# ScanDriver.net
KiCad netlist of a schematic drawn in EAGLE
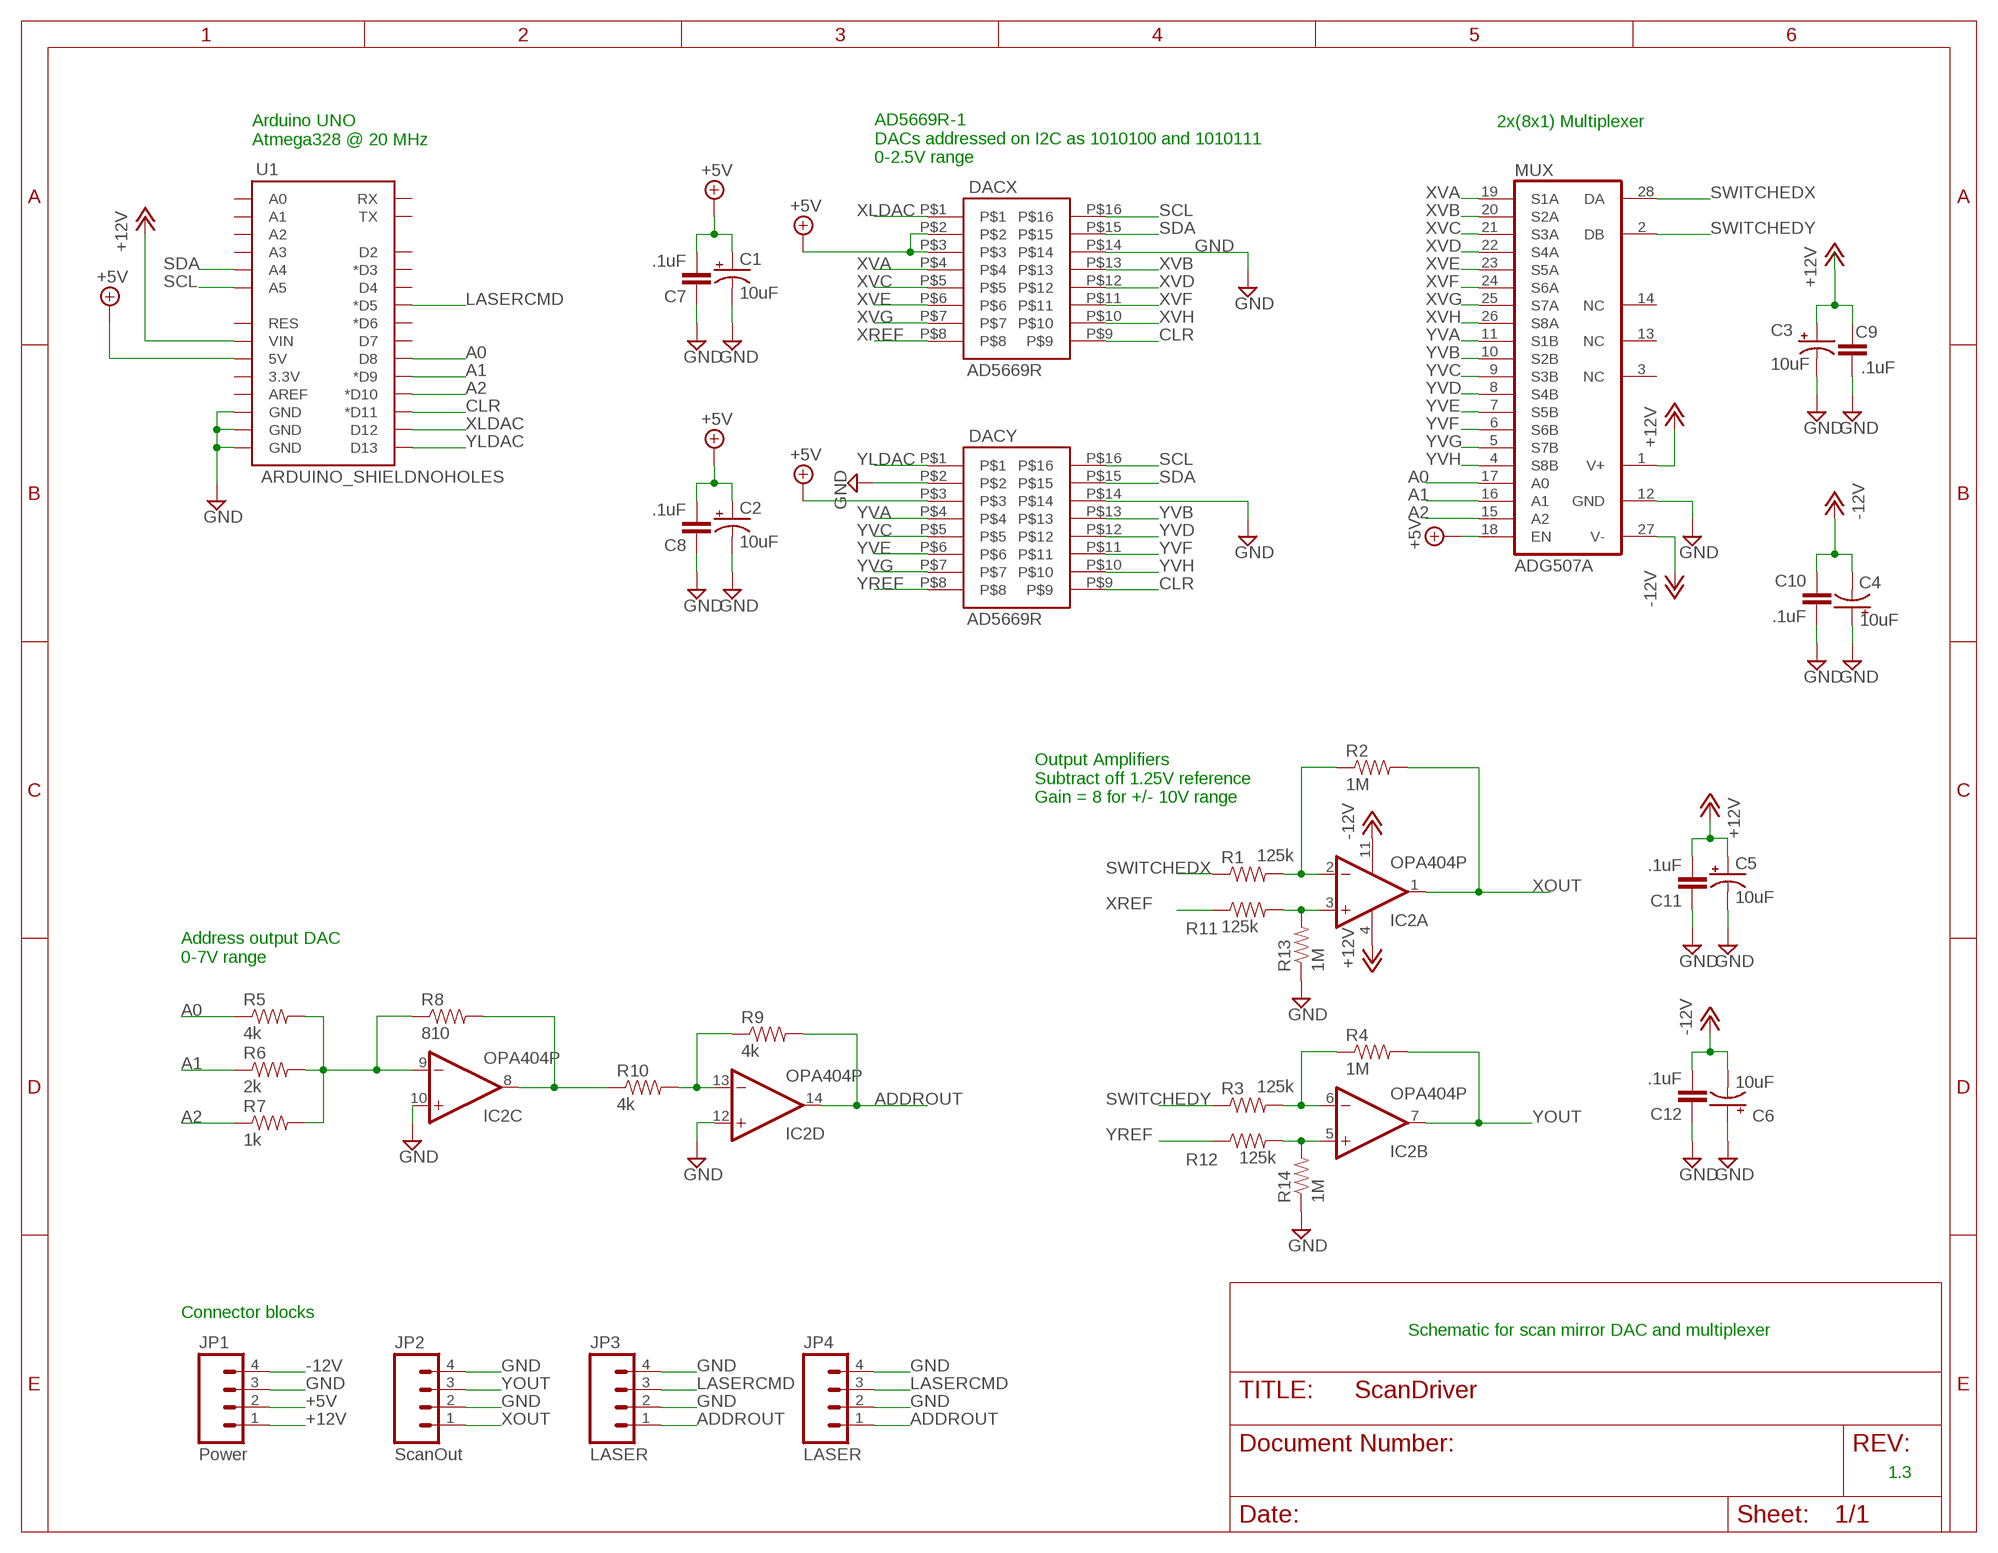
[diagram p0: schematic, sheet 1]

(export (version "E")
  (design (tool "Eeschema 10.0.6"))
  (components
    (comp (ref "C1")
      (value "10uF")
      (footprint "eagle-import:CPOL-RADIAL-10UF-25V")
      (libsource (lib "eagle-import") (part "CAP_POLPTH2"))
    )
    (comp (ref "C2")
      (value "10uF")
      (footprint "eagle-import:CPOL-RADIAL-10UF-25V")
      (libsource (lib "eagle-import") (part "CAP_POLPTH2"))
    )
    (comp (ref "C3")
      (value "10uF")
      (footprint "eagle-import:CPOL-RADIAL-10UF-25V")
      (libsource (lib "eagle-import") (part "CAP_POLPTH2"))
    )
    (comp (ref "C4")
      (value "10uF")
      (footprint "eagle-import:CPOL-RADIAL-10UF-25V")
      (libsource (lib "eagle-import") (part "CAP_POLPTH2"))
    )
    (comp (ref "C5")
      (value "10uF")
      (footprint "eagle-import:CPOL-RADIAL-10UF-25V")
      (libsource (lib "eagle-import") (part "CAP_POLPTH2"))
    )
    (comp (ref "C6")
      (value "10uF")
      (footprint "eagle-import:CPOL-RADIAL-10UF-25V")
      (libsource (lib "eagle-import") (part "CAP_POLPTH2"))
    )
    (comp (ref "C7")
      (value ".1uF")
      (footprint "eagle-import:CAP-PTH-SMALL-KIT")
      (libsource (lib "eagle-import") (part "CAPKIT"))
    )
    (comp (ref "C8")
      (value ".1uF")
      (footprint "eagle-import:CAP-PTH-SMALL-KIT")
      (libsource (lib "eagle-import") (part "CAPKIT"))
    )
    (comp (ref "C9")
      (value ".1uF")
      (footprint "eagle-import:CAP-PTH-SMALL-KIT")
      (libsource (lib "eagle-import") (part "CAPKIT"))
    )
    (comp (ref "C10")
      (value ".1uF")
      (footprint "eagle-import:CAP-PTH-SMALL-KIT")
      (libsource (lib "eagle-import") (part "CAPKIT"))
    )
    (comp (ref "C11")
      (value ".1uF")
      (footprint "eagle-import:CAP-PTH-SMALL-KIT")
      (libsource (lib "eagle-import") (part "CAPKIT"))
    )
    (comp (ref "C12")
      (value ".1uF")
      (footprint "eagle-import:CAP-PTH-SMALL-KIT")
      (libsource (lib "eagle-import") (part "CAPKIT"))
    )
    (comp (ref "DACX")
      (value "AD5669R")
      (footprint "eagle-import:SSOP16")
      (libsource (lib "eagle-import") (part "SSOP16"))
    )
    (comp (ref "DACY")
      (value "AD5669R")
      (footprint "eagle-import:SSOP16")
      (libsource (lib "eagle-import") (part "SSOP16"))
    )
    (comp (ref "IC2")
      (value "OPA404P")
      (footprint "eagle-import:DIL14")
      (libsource (lib "eagle-import") (part "OPA404P"))
    )
    (comp (ref "JP1")
      (value "Power")
      (footprint "eagle-import:MOLEX-1X4")
      (libsource (lib "eagle-import") (part "M04POLAR"))
    )
    (comp (ref "JP2")
      (value "ScanOut")
      (footprint "eagle-import:MOLEX-1X4")
      (libsource (lib "eagle-import") (part "M04POLAR"))
    )
    (comp (ref "JP3")
      (value "LASER")
      (footprint "eagle-import:MOLEX-1X4")
      (libsource (lib "eagle-import") (part "M04POLAR"))
    )
    (comp (ref "JP4")
      (value "LASER")
      (footprint "eagle-import:MOLEX-1X4")
      (libsource (lib "eagle-import") (part "M04POLAR"))
    )
    (comp (ref "MUX")
      (value "ADG507A")
      (footprint "eagle-import:DIL28-6")
      (fields (field (name "MPN") "DG507ACJ+"))
      (libsource (lib "eagle-import") (part "DG507ACJ"))
    )
    (comp (ref "R1")
      (value "125k")
      (footprint "eagle-import:AXIAL-0.4")
      (libsource (lib "eagle-import") (part "RESISTORPTH-1/4W"))
    )
    (comp (ref "R2")
      (value "1M")
      (footprint "eagle-import:AXIAL-0.4")
      (libsource (lib "eagle-import") (part "RESISTORPTH-1/4W"))
    )
    (comp (ref "R3")
      (value "125k")
      (footprint "eagle-import:AXIAL-0.4")
      (libsource (lib "eagle-import") (part "RESISTORPTH-1/4W"))
    )
    (comp (ref "R4")
      (value "1M")
      (footprint "eagle-import:AXIAL-0.4")
      (libsource (lib "eagle-import") (part "RESISTORPTH-1/4W"))
    )
    (comp (ref "R5")
      (value "4k")
      (footprint "eagle-import:AXIAL-0.4")
      (libsource (lib "eagle-import") (part "RESISTORPTH-1/4W"))
    )
    (comp (ref "R6")
      (value "2k")
      (footprint "eagle-import:AXIAL-0.4")
      (libsource (lib "eagle-import") (part "RESISTORPTH-1/4W"))
    )
    (comp (ref "R7")
      (value "1k")
      (footprint "eagle-import:AXIAL-0.4")
      (libsource (lib "eagle-import") (part "RESISTORPTH-1/4W"))
    )
    (comp (ref "R8")
      (value "810")
      (footprint "eagle-import:AXIAL-0.4")
      (libsource (lib "eagle-import") (part "RESISTORPTH-1/4W"))
    )
    (comp (ref "R9")
      (value "4k")
      (footprint "eagle-import:AXIAL-0.4")
      (libsource (lib "eagle-import") (part "RESISTORPTH-1/4W"))
    )
    (comp (ref "R10")
      (value "4k")
      (footprint "eagle-import:AXIAL-0.4")
      (libsource (lib "eagle-import") (part "RESISTORPTH-1/4W"))
    )
    (comp (ref "R11")
      (value "125k")
      (footprint "eagle-import:AXIAL-0.4")
      (libsource (lib "eagle-import") (part "RESISTORPTH-1/4W"))
    )
    (comp (ref "R12")
      (value "125k")
      (footprint "eagle-import:AXIAL-0.4")
      (libsource (lib "eagle-import") (part "RESISTORPTH-1/4W"))
    )
    (comp (ref "R13")
      (value "1M")
      (footprint "eagle-import:AXIAL-0.4")
      (libsource (lib "eagle-import") (part "RESISTORPTH-1/4W"))
    )
    (comp (ref "R14")
      (value "1M")
      (footprint "eagle-import:AXIAL-0.4")
      (libsource (lib "eagle-import") (part "RESISTORPTH-1/4W"))
    )
    (comp (ref "U1")
      (value "ARDUINO_SHIELDNOHOLES")
      (footprint "eagle-import:DUEMILANOVE_SHIELD_NOHOLES")
      (libsource (lib "eagle-import") (part "ARDUINO_SHIELDNOHOLES"))
    )
  )
  (nets
    (net (code "1") (name "+5V") (class "Default")
      (node (ref "C1") (pin "1") (pinfunction "+_1") (pintype "passive"))
      (node (ref "C2") (pin "1") (pinfunction "+_1") (pintype "passive"))
      (node (ref "C7") (pin "2") (pinfunction "2_2") (pintype "passive"))
      (node (ref "C8") (pin "2") (pinfunction "2_2") (pintype "passive"))
      (node (ref "DACX") (pin "P$2") (pinfunction "P$2_P$2") (pintype "bidirectional"))
      (node (ref "DACX") (pin "P$3") (pinfunction "P$3_P$3") (pintype "bidirectional"))
      (node (ref "DACY") (pin "P$3") (pinfunction "P$3_P$3") (pintype "bidirectional"))
      (node (ref "JP1") (pin "2") (pinfunction "2_2") (pintype "passive"))
      (node (ref "MUX") (pin "18") (pinfunction "EN_18") (pintype "input"))
      (node (ref "U1") (pin "5V") (pinfunction "5V_5V") (pintype "bidirectional"))
    )
    (net (code "2") (name "+12V") (class "Default")
      (node (ref "C11") (pin "2") (pinfunction "2_2") (pintype "passive"))
      (node (ref "C3") (pin "1") (pinfunction "+_1") (pintype "passive"))
      (node (ref "C5") (pin "1") (pinfunction "+_1") (pintype "passive"))
      (node (ref "C9") (pin "2") (pinfunction "2_2") (pintype "passive"))
      (node (ref "IC2") (pin "4") (pinfunction "V+_4") (pintype "power_in"))
      (node (ref "JP1") (pin "1") (pinfunction "1_1") (pintype "passive"))
      (node (ref "MUX") (pin "1") (pinfunction "V+_1") (pintype "power_in"))
      (node (ref "U1") (pin "VIN") (pinfunction "VIN_VIN") (pintype "bidirectional"))
    )
    (net (code "3") (name "-12V") (class "Default")
      (node (ref "C10") (pin "2") (pinfunction "2_2") (pintype "passive"))
      (node (ref "C12") (pin "2") (pinfunction "2_2") (pintype "passive"))
      (node (ref "C4") (pin "2") (pinfunction "-_2") (pintype "passive"))
      (node (ref "C6") (pin "2") (pinfunction "-_2") (pintype "passive"))
      (node (ref "IC2") (pin "11") (pinfunction "V-_11") (pintype "power_in"))
      (node (ref "JP1") (pin "4") (pinfunction "4_4") (pintype "passive"))
      (node (ref "MUX") (pin "27") (pinfunction "V-_27") (pintype "power_in"))
    )
    (net (code "4") (name "/A0") (class "Default")
      (node (ref "MUX") (pin "17") (pinfunction "A0_17") (pintype "input"))
      (node (ref "R5") (pin "P$1") (pinfunction "1_P$1") (pintype "passive"))
      (node (ref "U1") (pin "D8") (pinfunction "D8_D8") (pintype "bidirectional"))
    )
    (net (code "5") (name "/A1") (class "Default")
      (node (ref "MUX") (pin "16") (pinfunction "A1_16") (pintype "input"))
      (node (ref "R6") (pin "P$1") (pinfunction "1_P$1") (pintype "passive"))
      (node (ref "U1") (pin "D9") (pinfunction "*D9_D9") (pintype "bidirectional"))
    )
    (net (code "6") (name "/A2") (class "Default")
      (node (ref "MUX") (pin "15") (pinfunction "A2_15") (pintype "input"))
      (node (ref "R7") (pin "P$1") (pinfunction "1_P$1") (pintype "passive"))
      (node (ref "U1") (pin "D10") (pinfunction "*D10_D10") (pintype "bidirectional"))
    )
    (net (code "7") (name "/ADDROUT") (class "Default")
      (node (ref "IC2") (pin "14") (pinfunction "OUT_14") (pintype "output"))
      (node (ref "JP3") (pin "1") (pinfunction "1_1") (pintype "passive"))
      (node (ref "JP4") (pin "1") (pinfunction "1_1") (pintype "passive"))
      (node (ref "R9") (pin "P$2") (pinfunction "2_P$2") (pintype "passive"))
    )
    (net (code "8") (name "/CLR") (class "Default")
      (node (ref "DACX") (pin "P$9") (pinfunction "P$9_P$9") (pintype "bidirectional"))
      (node (ref "DACY") (pin "P$9") (pinfunction "P$9_P$9") (pintype "bidirectional"))
      (node (ref "U1") (pin "D11") (pinfunction "*D11_D11") (pintype "bidirectional"))
    )
    (net (code "9") (name "/LASERCMD") (class "Default")
      (node (ref "JP3") (pin "3") (pinfunction "3_3") (pintype "passive"))
      (node (ref "JP4") (pin "3") (pinfunction "3_3") (pintype "passive"))
      (node (ref "U1") (pin "D5") (pinfunction "*D5_D5") (pintype "bidirectional"))
    )
    (net (code "10") (name "/SCL") (class "Default")
      (node (ref "DACX") (pin "P$16") (pinfunction "P$16_P$16") (pintype "bidirectional"))
      (node (ref "DACY") (pin "P$16") (pinfunction "P$16_P$16") (pintype "bidirectional"))
      (node (ref "U1") (pin "A5") (pinfunction "A5_A5") (pintype "bidirectional"))
    )
    (net (code "11") (name "/SDA") (class "Default")
      (node (ref "DACX") (pin "P$15") (pinfunction "P$15_P$15") (pintype "bidirectional"))
      (node (ref "DACY") (pin "P$15") (pinfunction "P$15_P$15") (pintype "bidirectional"))
      (node (ref "U1") (pin "A4") (pinfunction "A4_A4") (pintype "bidirectional"))
    )
    (net (code "12") (name "/SWITCHEDX") (class "Default")
      (node (ref "MUX") (pin "28") (pinfunction "DA_28") (pintype "passive"))
      (node (ref "R1") (pin "P$1") (pinfunction "1_P$1") (pintype "passive"))
    )
    (net (code "13") (name "/SWITCHEDY") (class "Default")
      (node (ref "MUX") (pin "2") (pinfunction "DB_2") (pintype "passive"))
      (node (ref "R3") (pin "P$1") (pinfunction "1_P$1") (pintype "passive"))
    )
    (net (code "14") (name "/XLDAC") (class "Default")
      (node (ref "DACX") (pin "P$1") (pinfunction "P$1_P$1") (pintype "bidirectional"))
      (node (ref "U1") (pin "D12") (pinfunction "D12_D12") (pintype "bidirectional"))
    )
    (net (code "15") (name "/XOUT") (class "Default")
      (node (ref "IC2") (pin "1") (pinfunction "OUT_1") (pintype "output"))
      (node (ref "JP2") (pin "1") (pinfunction "1_1") (pintype "passive"))
      (node (ref "R2") (pin "P$2") (pinfunction "2_P$2") (pintype "passive"))
    )
    (net (code "16") (name "/XREF") (class "Default")
      (node (ref "DACX") (pin "P$8") (pinfunction "P$8_P$8") (pintype "bidirectional"))
      (node (ref "R11") (pin "P$1") (pinfunction "1_P$1") (pintype "passive"))
    )
    (net (code "17") (name "/XVA") (class "Default")
      (node (ref "DACX") (pin "P$4") (pinfunction "P$4_P$4") (pintype "bidirectional"))
      (node (ref "MUX") (pin "19") (pinfunction "S1A_19") (pintype "passive"))
    )
    (net (code "18") (name "/XVB") (class "Default")
      (node (ref "DACX") (pin "P$13") (pinfunction "P$13_P$13") (pintype "bidirectional"))
      (node (ref "MUX") (pin "20") (pinfunction "S2A_20") (pintype "passive"))
    )
    (net (code "19") (name "/XVC") (class "Default")
      (node (ref "DACX") (pin "P$5") (pinfunction "P$5_P$5") (pintype "bidirectional"))
      (node (ref "MUX") (pin "21") (pinfunction "S3A_21") (pintype "passive"))
    )
    (net (code "20") (name "/XVD") (class "Default")
      (node (ref "DACX") (pin "P$12") (pinfunction "P$12_P$12") (pintype "bidirectional"))
      (node (ref "MUX") (pin "22") (pinfunction "S4A_22") (pintype "passive"))
    )
    (net (code "21") (name "/XVE") (class "Default")
      (node (ref "DACX") (pin "P$6") (pinfunction "P$6_P$6") (pintype "bidirectional"))
      (node (ref "MUX") (pin "23") (pinfunction "S5A_23") (pintype "passive"))
    )
    (net (code "22") (name "/XVF") (class "Default")
      (node (ref "DACX") (pin "P$11") (pinfunction "P$11_P$11") (pintype "bidirectional"))
      (node (ref "MUX") (pin "24") (pinfunction "S6A_24") (pintype "passive"))
    )
    (net (code "23") (name "/XVG") (class "Default")
      (node (ref "DACX") (pin "P$7") (pinfunction "P$7_P$7") (pintype "bidirectional"))
      (node (ref "MUX") (pin "25") (pinfunction "S7A_25") (pintype "passive"))
    )
    (net (code "24") (name "/XVH") (class "Default")
      (node (ref "DACX") (pin "P$10") (pinfunction "P$10_P$10") (pintype "bidirectional"))
      (node (ref "MUX") (pin "26") (pinfunction "S8A_26") (pintype "passive"))
    )
    (net (code "25") (name "/YLDAC") (class "Default")
      (node (ref "DACY") (pin "P$1") (pinfunction "P$1_P$1") (pintype "bidirectional"))
      (node (ref "U1") (pin "D13") (pinfunction "D13_D13") (pintype "bidirectional"))
    )
    (net (code "26") (name "/YOUT") (class "Default")
      (node (ref "IC2") (pin "7") (pinfunction "OUT_7") (pintype "output"))
      (node (ref "JP2") (pin "3") (pinfunction "3_3") (pintype "passive"))
      (node (ref "R4") (pin "P$2") (pinfunction "2_P$2") (pintype "passive"))
    )
    (net (code "27") (name "/YREF") (class "Default")
      (node (ref "DACY") (pin "P$8") (pinfunction "P$8_P$8") (pintype "bidirectional"))
      (node (ref "R12") (pin "P$1") (pinfunction "1_P$1") (pintype "passive"))
    )
    (net (code "28") (name "/YVA") (class "Default")
      (node (ref "DACY") (pin "P$4") (pinfunction "P$4_P$4") (pintype "bidirectional"))
      (node (ref "MUX") (pin "11") (pinfunction "S1B_11") (pintype "passive"))
    )
    (net (code "29") (name "/YVB") (class "Default")
      (node (ref "DACY") (pin "P$13") (pinfunction "P$13_P$13") (pintype "bidirectional"))
      (node (ref "MUX") (pin "10") (pinfunction "S2B_10") (pintype "passive"))
    )
    (net (code "30") (name "/YVC") (class "Default")
      (node (ref "DACY") (pin "P$5") (pinfunction "P$5_P$5") (pintype "bidirectional"))
      (node (ref "MUX") (pin "9") (pinfunction "S3B_9") (pintype "passive"))
    )
    (net (code "31") (name "/YVD") (class "Default")
      (node (ref "DACY") (pin "P$12") (pinfunction "P$12_P$12") (pintype "bidirectional"))
      (node (ref "MUX") (pin "8") (pinfunction "S4B_8") (pintype "passive"))
    )
    (net (code "32") (name "/YVE") (class "Default")
      (node (ref "DACY") (pin "P$6") (pinfunction "P$6_P$6") (pintype "bidirectional"))
      (node (ref "MUX") (pin "7") (pinfunction "S5B_7") (pintype "passive"))
    )
    (net (code "33") (name "/YVF") (class "Default")
      (node (ref "DACY") (pin "P$11") (pinfunction "P$11_P$11") (pintype "bidirectional"))
      (node (ref "MUX") (pin "6") (pinfunction "S6B_6") (pintype "passive"))
    )
    (net (code "34") (name "/YVG") (class "Default")
      (node (ref "DACY") (pin "P$7") (pinfunction "P$7_P$7") (pintype "bidirectional"))
      (node (ref "MUX") (pin "5") (pinfunction "S7B_5") (pintype "passive"))
    )
    (net (code "35") (name "/YVH") (class "Default")
      (node (ref "DACY") (pin "P$10") (pinfunction "P$10_P$10") (pintype "bidirectional"))
      (node (ref "MUX") (pin "4") (pinfunction "S8B_4") (pintype "passive"))
    )
    (net (code "36") (name "GND") (class "Default")
      (node (ref "C1") (pin "2") (pinfunction "-_2") (pintype "passive"))
      (node (ref "C10") (pin "1") (pinfunction "1_1") (pintype "passive"))
      (node (ref "C11") (pin "1") (pinfunction "1_1") (pintype "passive"))
      (node (ref "C12") (pin "1") (pinfunction "1_1") (pintype "passive"))
      (node (ref "C2") (pin "2") (pinfunction "-_2") (pintype "passive"))
      (node (ref "C3") (pin "2") (pinfunction "-_2") (pintype "passive"))
      (node (ref "C4") (pin "1") (pinfunction "+_1") (pintype "passive"))
      (node (ref "C5") (pin "2") (pinfunction "-_2") (pintype "passive"))
      (node (ref "C6") (pin "1") (pinfunction "+_1") (pintype "passive"))
      (node (ref "C7") (pin "1") (pinfunction "1_1") (pintype "passive"))
      (node (ref "C8") (pin "1") (pinfunction "1_1") (pintype "passive"))
      (node (ref "C9") (pin "1") (pinfunction "1_1") (pintype "passive"))
      (node (ref "DACX") (pin "P$14") (pinfunction "P$14_P$14") (pintype "bidirectional"))
      (node (ref "DACY") (pin "P$14") (pinfunction "P$14_P$14") (pintype "bidirectional"))
      (node (ref "DACY") (pin "P$2") (pinfunction "P$2_P$2") (pintype "bidirectional"))
      (node (ref "IC2") (pin "10") (pinfunction "+IN_10") (pintype "input"))
      (node (ref "IC2") (pin "12") (pinfunction "+IN_12") (pintype "input"))
      (node (ref "JP1") (pin "3") (pinfunction "3_3") (pintype "passive"))
      (node (ref "JP2") (pin "2") (pinfunction "2_2") (pintype "passive"))
      (node (ref "JP2") (pin "4") (pinfunction "4_4") (pintype "passive"))
      (node (ref "JP3") (pin "2") (pinfunction "2_2") (pintype "passive"))
      (node (ref "JP3") (pin "4") (pinfunction "4_4") (pintype "passive"))
      (node (ref "JP4") (pin "2") (pinfunction "2_2") (pintype "passive"))
      (node (ref "JP4") (pin "4") (pinfunction "4_4") (pintype "passive"))
      (node (ref "MUX") (pin "12") (pinfunction "GND_12") (pintype "power_in"))
      (node (ref "R13") (pin "P$1") (pinfunction "1_P$1") (pintype "passive"))
      (node (ref "R14") (pin "P$1") (pinfunction "1_P$1") (pintype "passive"))
      (node (ref "U1") (pin "GND@0") (pinfunction "GND_GND@0") (pintype "bidirectional"))
      (node (ref "U1") (pin "GND@1") (pinfunction "GND_GND@1") (pintype "bidirectional"))
      (node (ref "U1") (pin "GND@2") (pinfunction "GND_GND@2") (pintype "bidirectional"))
    )
    (net (code "37") (name "Net-(IC2A-+IN)") (class "Default")
      (node (ref "IC2") (pin "3") (pinfunction "+IN_3") (pintype "input"))
      (node (ref "R11") (pin "P$2") (pinfunction "2_P$2") (pintype "passive"))
      (node (ref "R13") (pin "P$2") (pinfunction "2_P$2") (pintype "passive"))
    )
    (net (code "38") (name "Net-(IC2A--IN)") (class "Default")
      (node (ref "IC2") (pin "2") (pinfunction "-IN_2") (pintype "input"))
      (node (ref "R1") (pin "P$2") (pinfunction "2_P$2") (pintype "passive"))
      (node (ref "R2") (pin "P$1") (pinfunction "1_P$1") (pintype "passive"))
    )
    (net (code "39") (name "Net-(IC2B-+IN)") (class "Default")
      (node (ref "IC2") (pin "5") (pinfunction "+IN_5") (pintype "input"))
      (node (ref "R12") (pin "P$2") (pinfunction "2_P$2") (pintype "passive"))
      (node (ref "R14") (pin "P$2") (pinfunction "2_P$2") (pintype "passive"))
    )
    (net (code "40") (name "Net-(IC2B--IN)") (class "Default")
      (node (ref "IC2") (pin "6") (pinfunction "-IN_6") (pintype "input"))
      (node (ref "R3") (pin "P$2") (pinfunction "2_P$2") (pintype "passive"))
      (node (ref "R4") (pin "P$1") (pinfunction "1_P$1") (pintype "passive"))
    )
    (net (code "41") (name "Net-(IC2C--IN)") (class "Default")
      (node (ref "IC2") (pin "9") (pinfunction "-IN_9") (pintype "input"))
      (node (ref "R5") (pin "P$2") (pinfunction "2_P$2") (pintype "passive"))
      (node (ref "R6") (pin "P$2") (pinfunction "2_P$2") (pintype "passive"))
      (node (ref "R7") (pin "P$2") (pinfunction "2_P$2") (pintype "passive"))
      (node (ref "R8") (pin "P$1") (pinfunction "1_P$1") (pintype "passive"))
    )
    (net (code "42") (name "Net-(IC2C-OUT)") (class "Default")
      (node (ref "IC2") (pin "8") (pinfunction "OUT_8") (pintype "output"))
      (node (ref "R10") (pin "P$1") (pinfunction "1_P$1") (pintype "passive"))
      (node (ref "R8") (pin "P$2") (pinfunction "2_P$2") (pintype "passive"))
    )
    (net (code "43") (name "Net-(IC2D--IN)") (class "Default")
      (node (ref "IC2") (pin "13") (pinfunction "-IN_13") (pintype "input"))
      (node (ref "R10") (pin "P$2") (pinfunction "2_P$2") (pintype "passive"))
      (node (ref "R9") (pin "P$1") (pinfunction "1_P$1") (pintype "passive"))
    )
    (net (code "44") (name "unconnected-(MUX-NC-Pad3)") (class "Default")
      (node (ref "MUX") (pin "3") (pinfunction "NC_3") (pintype "no_connect"))
    )
    (net (code "45") (name "unconnected-(MUX-NC-Pad13)") (class "Default")
      (node (ref "MUX") (pin "13") (pinfunction "NC_13") (pintype "no_connect"))
    )
    (net (code "46") (name "unconnected-(MUX-NC-Pad14)") (class "Default")
      (node (ref "MUX") (pin "14") (pinfunction "NC_14") (pintype "no_connect"))
    )
    (net (code "47") (name "unconnected-(U1-*D3-PadD3)") (class "Default")
      (node (ref "U1") (pin "D3") (pinfunction "*D3_D3") (pintype "bidirectional"))
    )
    (net (code "48") (name "unconnected-(U1-*D6-PadD6)") (class "Default")
      (node (ref "U1") (pin "D6") (pinfunction "*D6_D6") (pintype "bidirectional"))
    )
    (net (code "49") (name "unconnected-(U1-Pad3.3V)") (class "Default")
      (node (ref "U1") (pin "3.3V") (pinfunction "3.3V_3.3V") (pintype "bidirectional"))
    )
    (net (code "50") (name "unconnected-(U1-PadA0)") (class "Default")
      (node (ref "U1") (pin "A0") (pinfunction "A0_A0") (pintype "bidirectional"))
    )
    (net (code "51") (name "unconnected-(U1-PadA1)") (class "Default")
      (node (ref "U1") (pin "A1") (pinfunction "A1_A1") (pintype "bidirectional"))
    )
    (net (code "52") (name "unconnected-(U1-PadA2)") (class "Default")
      (node (ref "U1") (pin "A2") (pinfunction "A2_A2") (pintype "bidirectional"))
    )
    (net (code "53") (name "unconnected-(U1-PadA3)") (class "Default")
      (node (ref "U1") (pin "A3") (pinfunction "A3_A3") (pintype "bidirectional"))
    )
    (net (code "54") (name "unconnected-(U1-PadAREF)") (class "Default")
      (node (ref "U1") (pin "AREF") (pinfunction "AREF_AREF") (pintype "bidirectional"))
    )
    (net (code "55") (name "unconnected-(U1-PadD2)") (class "Default")
      (node (ref "U1") (pin "D2") (pinfunction "D2_D2") (pintype "bidirectional"))
    )
    (net (code "56") (name "unconnected-(U1-PadD4)") (class "Default")
      (node (ref "U1") (pin "D4") (pinfunction "D4_D4") (pintype "bidirectional"))
    )
    (net (code "57") (name "unconnected-(U1-PadD7)") (class "Default")
      (node (ref "U1") (pin "D7") (pinfunction "D7_D7") (pintype "bidirectional"))
    )
    (net (code "58") (name "unconnected-(U1-PadRES)") (class "Default")
      (node (ref "U1") (pin "RES") (pinfunction "RES_RES") (pintype "bidirectional"))
    )
    (net (code "59") (name "unconnected-(U1-PadRX)") (class "Default")
      (node (ref "U1") (pin "RX") (pinfunction "RX_RX") (pintype "bidirectional"))
    )
    (net (code "60") (name "unconnected-(U1-PadTX)") (class "Default")
      (node (ref "U1") (pin "TX") (pinfunction "TX_TX") (pintype "bidirectional"))
    )
  )
)
